# MercurialSDR_PWR_with_dual_option.net
KiCad netlist of a schematic drawn in Altium Designer
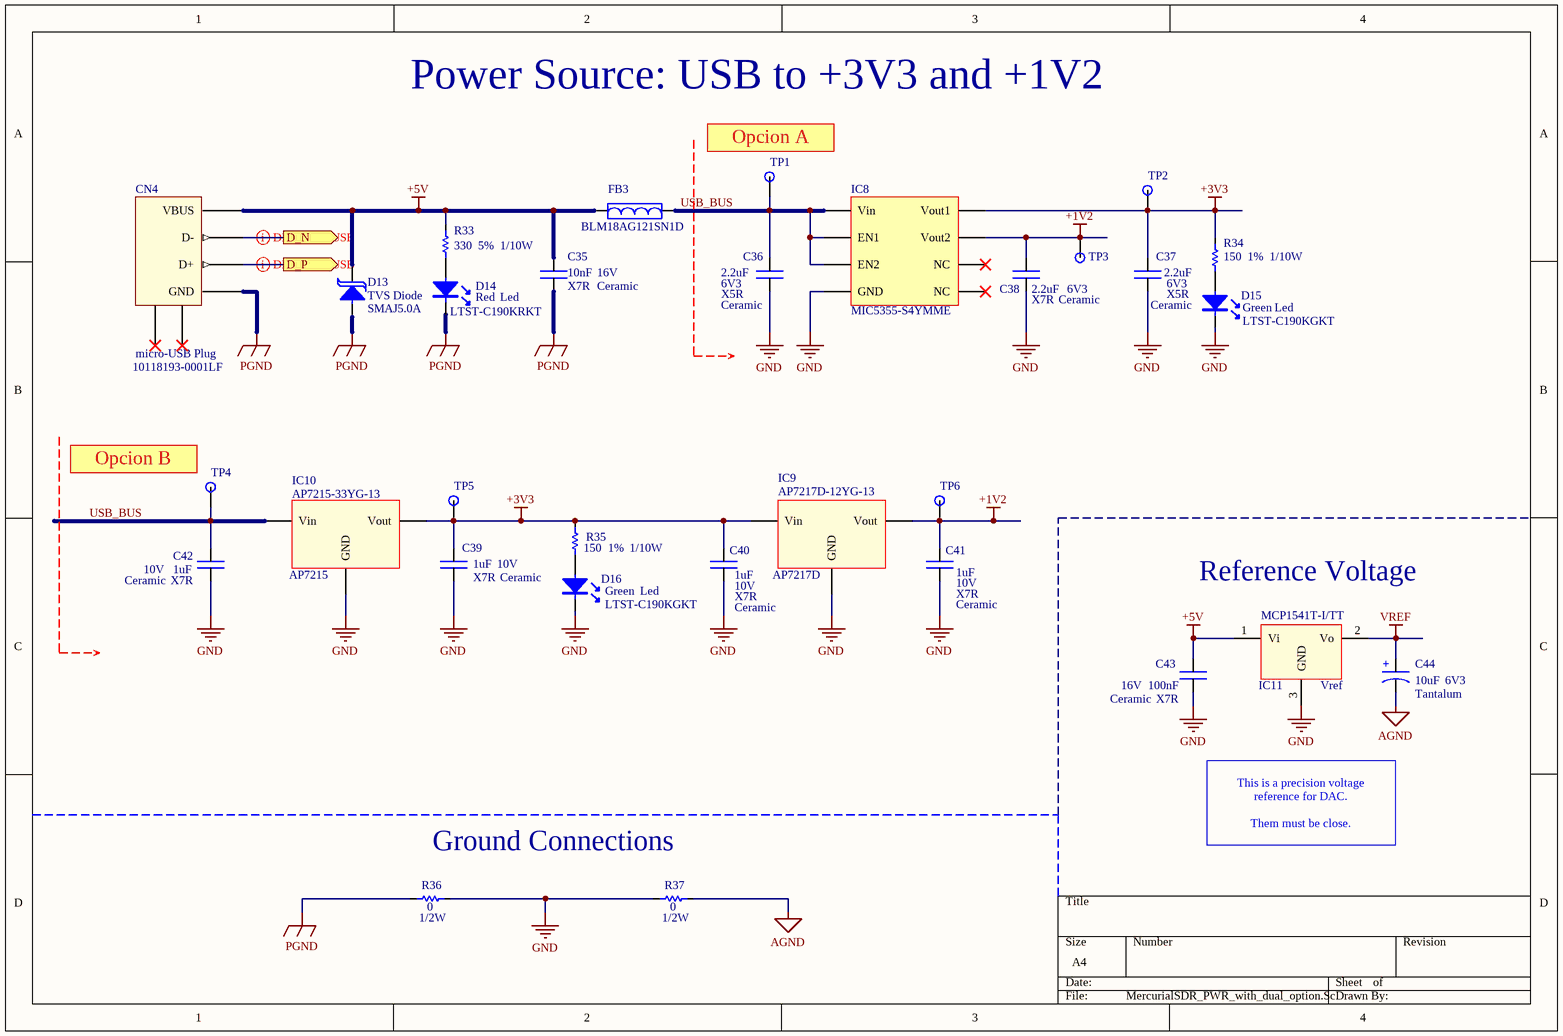
[diagram p0: MercurialSDR_PWR_with_dual_option.SchDoc]

(export (version "E")
  (design (tool "Eeschema 10.0.6"))
  (components
    (comp (ref "C35")
      (value "10nF")
      (footprint "CAP_0603")
      (description "Capacitor no polarizado")
      (fields
        (field (name "TEMP COEF") "X7R")
        (field (name "PART NUMBER") "CC0603KRX7R7BB103")
        (field (name "VR") "16V")
        (field (name "MATERIAL") "Ceramic")
        (field (name "Comment") "Capacitor")
      )
      (libsource (lib "MercurialSDR") (part "Cap"))
    )
    (comp (ref "C36")
      (value "2.2uF")
      (footprint "CAP_0603")
      (description "Capacitor no polarizado")
      (fields
        (field (name "TEMP COEF") "X5R")
        (field (name "PART NUMBER") "CL10A225KQ8NNNC")
        (field (name "VR") "6V3")
        (field (name "MATERIAL") "Ceramic")
        (field (name "Comment") "Capacitor")
      )
      (libsource (lib "MercurialSDR") (part "Cap"))
    )
    (comp (ref "C37")
      (value "2.2uF")
      (footprint "CAP_0603")
      (description "Capacitor no polarizado")
      (fields
        (field (name "TEMP COEF") "X5R")
        (field (name "PART NUMBER") "CL10A225KQ8NNNC")
        (field (name "VR") "6V3")
        (field (name "MATERIAL") "Ceramic")
        (field (name "Comment") "Capacitor")
      )
      (libsource (lib "MercurialSDR") (part "Cap"))
    )
    (comp (ref "C38")
      (value "2.2uF")
      (footprint "CAP_0603")
      (description "Capacitor no polarizado")
      (fields
        (field (name "TEMP COEF") "X7R")
        (field (name "PART NUMBER") "CL10B225KQ8NFNC")
        (field (name "VR") "6V3")
        (field (name "MATERIAL") "Ceramic")
        (field (name "Comment") "Capacitor")
      )
      (libsource (lib "MercurialSDR") (part "Cap"))
    )
    (comp (ref "C39")
      (value "1uF")
      (footprint "CAP_0603")
      (description "Capacitor no polarizado")
      (fields
        (field (name "TEMP COEF") "X7R")
        (field (name "PART NUMBER") "CL10B105KP8NNNC")
        (field (name "VR") "10V")
        (field (name "MATERIAL") "Ceramic")
        (field (name "Comment") "Capacitor")
      )
      (libsource (lib "MercurialSDR") (part "Cap"))
    )
    (comp (ref "C40")
      (value "1uF")
      (footprint "CAP_0603")
      (description "Capacitor no polarizado")
      (fields
        (field (name "TEMP COEF") "X7R")
        (field (name "PART NUMBER") "CL10B105KP8NNNC")
        (field (name "VR") "10V")
        (field (name "MATERIAL") "Ceramic")
        (field (name "Comment") "Capacitor")
      )
      (libsource (lib "MercurialSDR") (part "Cap"))
    )
    (comp (ref "C41")
      (value "1uF")
      (footprint "CAP_0603")
      (description "Capacitor no polarizado")
      (fields
        (field (name "TEMP COEF") "X7R")
        (field (name "PART NUMBER") "CL10B105KP8NNNC")
        (field (name "VR") "10V")
        (field (name "MATERIAL") "Ceramic")
        (field (name "Comment") "Capacitor")
      )
      (libsource (lib "MercurialSDR") (part "Cap"))
    )
    (comp (ref "C42")
      (value "1uF")
      (footprint "CAP_0603")
      (description "Capacitor no polarizado")
      (fields
        (field (name "TEMP COEF") "X7R")
        (field (name "PART NUMBER") "CL10B105KP8NNNC")
        (field (name "VR") "10V")
        (field (name "MATERIAL") "Ceramic")
        (field (name "Comment") "Capacitor")
      )
      (libsource (lib "MercurialSDR") (part "Cap"))
    )
    (comp (ref "C43")
      (value "100nF")
      (footprint "CAP_0603")
      (description "Capacitor no polarizado")
      (fields
        (field (name "TEMP COEF") "X7R")
        (field (name "PART NUMBER") "CL10B104KO8NNNC")
        (field (name "VR") "16V")
        (field (name "MATERIAL") "Ceramic")
        (field (name "Comment") "Capacitor")
      )
      (libsource (lib "MercurialSDR") (part "Cap"))
    )
    (comp (ref "C44")
      (value "10uF")
      (footprint "CAP_TANT_1206")
      (description "Capacitor polarizado")
      (fields
        (field (name "PART NUMBER") "TAJA106K006RNJ")
        (field (name "VR") "6V3")
        (field (name "MATERIAL") "Tantalum")
        (field (name "Comment") "Capacitor Polarizado")
      )
      (libsource (lib "MercurialSDR") (part "Cap Pol"))
    )
    (comp (ref "CN4")
      (value "micro-USB Plug")
      (footprint "USB_Micro")
      (description "USB Plug")
      (fields (field (name "PART NUMBER") "10118193-0001LF"))
      (libsource (lib "MercurialSDR") (part "USB Plug"))
    )
    (comp (ref "D13")
      (value "TVS Diode")
      (footprint "DO-214AC")
      (description "TVS (Supresor de transitorios)")
      (fields (field (name "PART NUMBER") "SMAJ5.0A"))
      (libsource (lib "MercurialSDR") (part "TVS_DIODE"))
    )
    (comp (ref "D14")
      (value "Led")
      (footprint "LED_0603")
      (fields (field (name "COLOR") "Red") (field (name "PART NUMBER") "LTST-C190KRKT"))
      (libsource (lib "MercurialSDR") (part "Led"))
    )
    (comp (ref "D15")
      (value "Led")
      (footprint "LED_0603")
      (fields (field (name "COLOR") "Green") (field (name "PART NUMBER") "LTST-C190KGKT"))
      (libsource (lib "MercurialSDR") (part "Led"))
    )
    (comp (ref "D16")
      (value "Led")
      (footprint "LED_0603")
      (fields (field (name "COLOR") "Green") (field (name "PART NUMBER") "LTST-C190KGKT"))
      (libsource (lib "MercurialSDR") (part "Led"))
    )
    (comp (ref "FB3")
      (value "Ferrite Bead")
      (footprint "FERRITE_BEAD_0603")
      (fields (field (name "PART NUMBER") "BLM18AG121SN1D"))
      (libsource (lib "MercurialSDR") (part "Ferrite Bead"))
    )
    (comp (ref "IC8")
      (value "MIC5355")
      (footprint "MSOP-8")
      (description "Linea Regulator Dual")
      (fields (field (name "PART NUMBER") "MIC5355-S4YMME"))
      (libsource (lib "MercurialSDR") (part "MIC5355"))
    )
    (comp (ref "IC9")
      (value "AP7217D")
      (footprint "SOT89-3L")
      (description "Linear Voltage Regulator 1V2")
      (fields (field (name "PART NUMBER") "AP7217D-12YG-13"))
      (libsource (lib "MercurialSDR") (part "AP7217D"))
    )
    (comp (ref "IC10")
      (value "AP7215")
      (footprint "SOT89-3L")
      (description "Linear Voltage Regulator 3v3")
      (fields (field (name "PART NUMBER") "AP7215-33YG-13"))
      (libsource (lib "MercurialSDR") (part "AP7215"))
    )
    (comp (ref "IC11")
      (value "Vref")
      (footprint "SOT-23-3")
      (description "Reference Voltage")
      (fields (field (name "PART NUMBER") "MCP1541T-I/TT"))
      (libsource (lib "MercurialSDR") (part "MCP1541"))
    )
    (comp (ref "R33")
      (value "330")
      (footprint "RES_0603")
      (description "Resistor")
      (fields
        (field (name "POWER") "1/10W")
        (field (name "PART NUMBER") "CR0603-JW-331ELF")
        (field (name "TOLERANCE") "5%")
        (field (name "Comment") "Resistor SMD")
      )
      (libsource (lib "MercurialSDR") (part "Res"))
    )
    (comp (ref "R34")
      (value "150")
      (footprint "RES_0603")
      (description "Resistor")
      (fields
        (field (name "POWER") "1/10W")
        (field (name "PART NUMBER") "ERJ-3EKF1500V")
        (field (name "TOLERANCE") "1%")
        (field (name "Comment") "Resistor SMD")
      )
      (libsource (lib "MercurialSDR") (part "Res"))
    )
    (comp (ref "R35")
      (value "150")
      (footprint "RES_0603")
      (description "Resistor")
      (fields
        (field (name "POWER") "1/10W")
        (field (name "PART NUMBER") "ERJ-3EKF1500V")
        (field (name "TOLERANCE") "1%")
        (field (name "Comment") "Resistor SMD")
      )
      (libsource (lib "MercurialSDR") (part "Res"))
    )
    (comp (ref "R36")
      (value "0")
      (footprint "0805")
      (description "Resistor")
      (fields
        (field (name "POWER") "1/2W")
        (field (name "PART NUMBER") "CRCW08050000Z0EAHP")
        (field (name "Comment") "Resistor SMD")
      )
      (libsource (lib "MercurialSDR") (part "Res"))
    )
    (comp (ref "R37")
      (value "0")
      (footprint "0805")
      (description "Resistor")
      (fields
        (field (name "POWER") "1/2W")
        (field (name "PART NUMBER") "CRCW08050000Z0EAHP")
        (field (name "Comment") "Resistor SMD")
      )
      (libsource (lib "MercurialSDR") (part "Res"))
    )
    (comp (ref "TP1") (value "Test Point") (libsource (lib "MercurialSDR") (part "Test Point")))
    (comp (ref "TP2") (value "Test Point") (libsource (lib "MercurialSDR") (part "Test Point")))
    (comp (ref "TP3") (value "Test Point") (libsource (lib "MercurialSDR") (part "Test Point")))
    (comp (ref "TP4") (value "Test Point") (libsource (lib "MercurialSDR") (part "Test Point")))
    (comp (ref "TP5") (value "Test Point") (libsource (lib "MercurialSDR") (part "Test Point")))
    (comp (ref "TP6") (value "Test Point") (libsource (lib "MercurialSDR") (part "Test Point")))
  )
  (nets
    (net (code "1") (name "+1V2") (class "Default")
      (node (ref "C38") (pin "1") (pinfunction "1_1") (pintype "passive"))
      (node (ref "C41") (pin "1") (pinfunction "1_1") (pintype "passive"))
      (node (ref "IC8") (pin "7") (pinfunction "Vout2_7") (pintype "passive"))
      (node (ref "IC9") (pin "3") (pinfunction "Vout_3") (pintype "passive"))
      (node (ref "TP3") (pin "1") (pinfunction "TP?_1") (pintype "passive"))
      (node (ref "TP6") (pin "1") (pinfunction "TP?_1") (pintype "passive"))
    )
    (net (code "2") (name "+3V3") (class "Default")
      (node (ref "C37") (pin "1") (pinfunction "1_1") (pintype "passive"))
      (node (ref "C39") (pin "1") (pinfunction "1_1") (pintype "passive"))
      (node (ref "C40") (pin "1") (pinfunction "1_1") (pintype "passive"))
      (node (ref "IC10") (pin "3") (pinfunction "Vout_3") (pintype "passive"))
      (node (ref "IC8") (pin "8") (pinfunction "Vout1_8") (pintype "passive"))
      (node (ref "IC9") (pin "2") (pinfunction "Vin_2") (pintype "passive"))
      (node (ref "R34") (pin "1") (pinfunction "1_1") (pintype "passive"))
      (node (ref "R35") (pin "1") (pinfunction "1_1") (pintype "passive"))
      (node (ref "TP2") (pin "1") (pinfunction "TP?_1") (pintype "passive"))
      (node (ref "TP5") (pin "1") (pinfunction "TP?_1") (pintype "passive"))
    )
    (net (code "3") (name "+5V") (class "Default")
      (node (ref "C35") (pin "1") (pinfunction "1_1") (pintype "passive"))
      (node (ref "C43") (pin "1") (pinfunction "1_1") (pintype "passive"))
      (node (ref "CN4") (pin "1") (pinfunction "VBUS_1") (pintype "power_in"))
      (node (ref "D13") (pin "2") (pinfunction "K_2") (pintype "passive"))
      (node (ref "FB3") (pin "1") (pinfunction "1_1") (pintype "passive"))
      (node (ref "IC11") (pin "1") (pinfunction "Vi_1") (pintype "passive"))
      (node (ref "R33") (pin "1") (pinfunction "1_1") (pintype "passive"))
    )
    (net (code "4") (name "/D_N") (class "Default")
      (node (ref "CN4") (pin "2") (pinfunction "D-_2") (pintype "output"))
    )
    (net (code "5") (name "/D_P") (class "Default")
      (node (ref "CN4") (pin "3") (pinfunction "D+_3") (pintype "output"))
    )
    (net (code "6") (name "/USB_BUS") (class "Default")
      (node (ref "C36") (pin "1") (pinfunction "1_1") (pintype "passive"))
      (node (ref "C42") (pin "1") (pinfunction "1_1") (pintype "passive"))
      (node (ref "FB3") (pin "2") (pinfunction "2_2") (pintype "passive"))
      (node (ref "IC10") (pin "2") (pinfunction "Vin_2") (pintype "passive"))
      (node (ref "IC8") (pin "1") (pinfunction "Vin_1") (pintype "passive"))
      (node (ref "IC8") (pin "4") (pinfunction "EN2_4") (pintype "passive"))
      (node (ref "IC8") (pin "5") (pinfunction "EN1_5") (pintype "passive"))
      (node (ref "TP1") (pin "1") (pinfunction "TP?_1") (pintype "passive"))
      (node (ref "TP4") (pin "1") (pinfunction "TP?_1") (pintype "passive"))
    )
    (net (code "7") (name "AGND") (class "Default")
      (node (ref "C44") (pin "2") (pinfunction "2_2") (pintype "passive"))
      (node (ref "R37") (pin "1") (pinfunction "1_1") (pintype "passive"))
    )
    (net (code "8") (name "GND") (class "Default")
      (node (ref "C36") (pin "2") (pinfunction "2_2") (pintype "passive"))
      (node (ref "C37") (pin "2") (pinfunction "2_2") (pintype "passive"))
      (node (ref "C38") (pin "2") (pinfunction "2_2") (pintype "passive"))
      (node (ref "C39") (pin "2") (pinfunction "2_2") (pintype "passive"))
      (node (ref "C40") (pin "2") (pinfunction "2_2") (pintype "passive"))
      (node (ref "C41") (pin "2") (pinfunction "2_2") (pintype "passive"))
      (node (ref "C42") (pin "2") (pinfunction "2_2") (pintype "passive"))
      (node (ref "C43") (pin "2") (pinfunction "2_2") (pintype "passive"))
      (node (ref "D15") (pin "2") (pinfunction "K_2") (pintype "passive"))
      (node (ref "D16") (pin "2") (pinfunction "K_2") (pintype "passive"))
      (node (ref "IC10") (pin "1") (pinfunction "GND_1") (pintype "passive"))
      (node (ref "IC11") (pin "3") (pinfunction "GND_3") (pintype "passive"))
      (node (ref "IC8") (pin "2") (pinfunction "GND_2") (pintype "passive"))
      (node (ref "IC9") (pin "1") (pinfunction "GND_1") (pintype "passive"))
      (node (ref "R36") (pin "1") (pinfunction "1_1") (pintype "passive"))
      (node (ref "R37") (pin "2") (pinfunction "2_2") (pintype "passive"))
    )
    (net (code "9") (name "Net-(D14-A)") (class "Default")
      (node (ref "D14") (pin "1") (pinfunction "A_1") (pintype "passive"))
      (node (ref "R33") (pin "2") (pinfunction "2_2") (pintype "passive"))
    )
    (net (code "10") (name "Net-(D15-A)") (class "Default")
      (node (ref "D15") (pin "1") (pinfunction "A_1") (pintype "passive"))
      (node (ref "R34") (pin "2") (pinfunction "2_2") (pintype "passive"))
    )
    (net (code "11") (name "Net-(D16-A)") (class "Default")
      (node (ref "D16") (pin "1") (pinfunction "A_1") (pintype "passive"))
      (node (ref "R35") (pin "2") (pinfunction "2_2") (pintype "passive"))
    )
    (net (code "12") (name "PGND") (class "Default")
      (node (ref "C35") (pin "2") (pinfunction "2_2") (pintype "passive"))
      (node (ref "CN4") (pin "4") (pinfunction "GND_4") (pintype "power_in"))
      (node (ref "D13") (pin "1") (pinfunction "A_1") (pintype "passive"))
      (node (ref "D14") (pin "2") (pinfunction "K_2") (pintype "passive"))
      (node (ref "R36") (pin "2") (pinfunction "2_2") (pintype "passive"))
    )
    (net (code "13") (name "VREF") (class "Default")
      (node (ref "C44") (pin "1") (pinfunction "1_1") (pintype "passive"))
      (node (ref "IC11") (pin "2") (pinfunction "Vo_2") (pintype "passive"))
    )
    (net (code "14") (name "unconnected-(CN4-Shield-Pad5)") (class "Default")
      (node (ref "CN4") (pin "5") (pinfunction "Shield_5") (pintype "passive+no_connect"))
    )
    (net (code "15") (name "unconnected-(CN4-Shield-Pad6)") (class "Default")
      (node (ref "CN4") (pin "6") (pinfunction "Shield_6") (pintype "passive+no_connect"))
    )
    (net (code "16") (name "unconnected-(IC8-NC-Pad3)") (class "Default")
      (node (ref "IC8") (pin "3") (pinfunction "NC_3") (pintype "passive+no_connect"))
    )
    (net (code "17") (name "unconnected-(IC8-NC-Pad6)") (class "Default")
      (node (ref "IC8") (pin "6") (pinfunction "NC_6") (pintype "passive+no_connect"))
    )
  )
)
